# comando.net
KiCad netlist of a schematic drawn in EAGLE
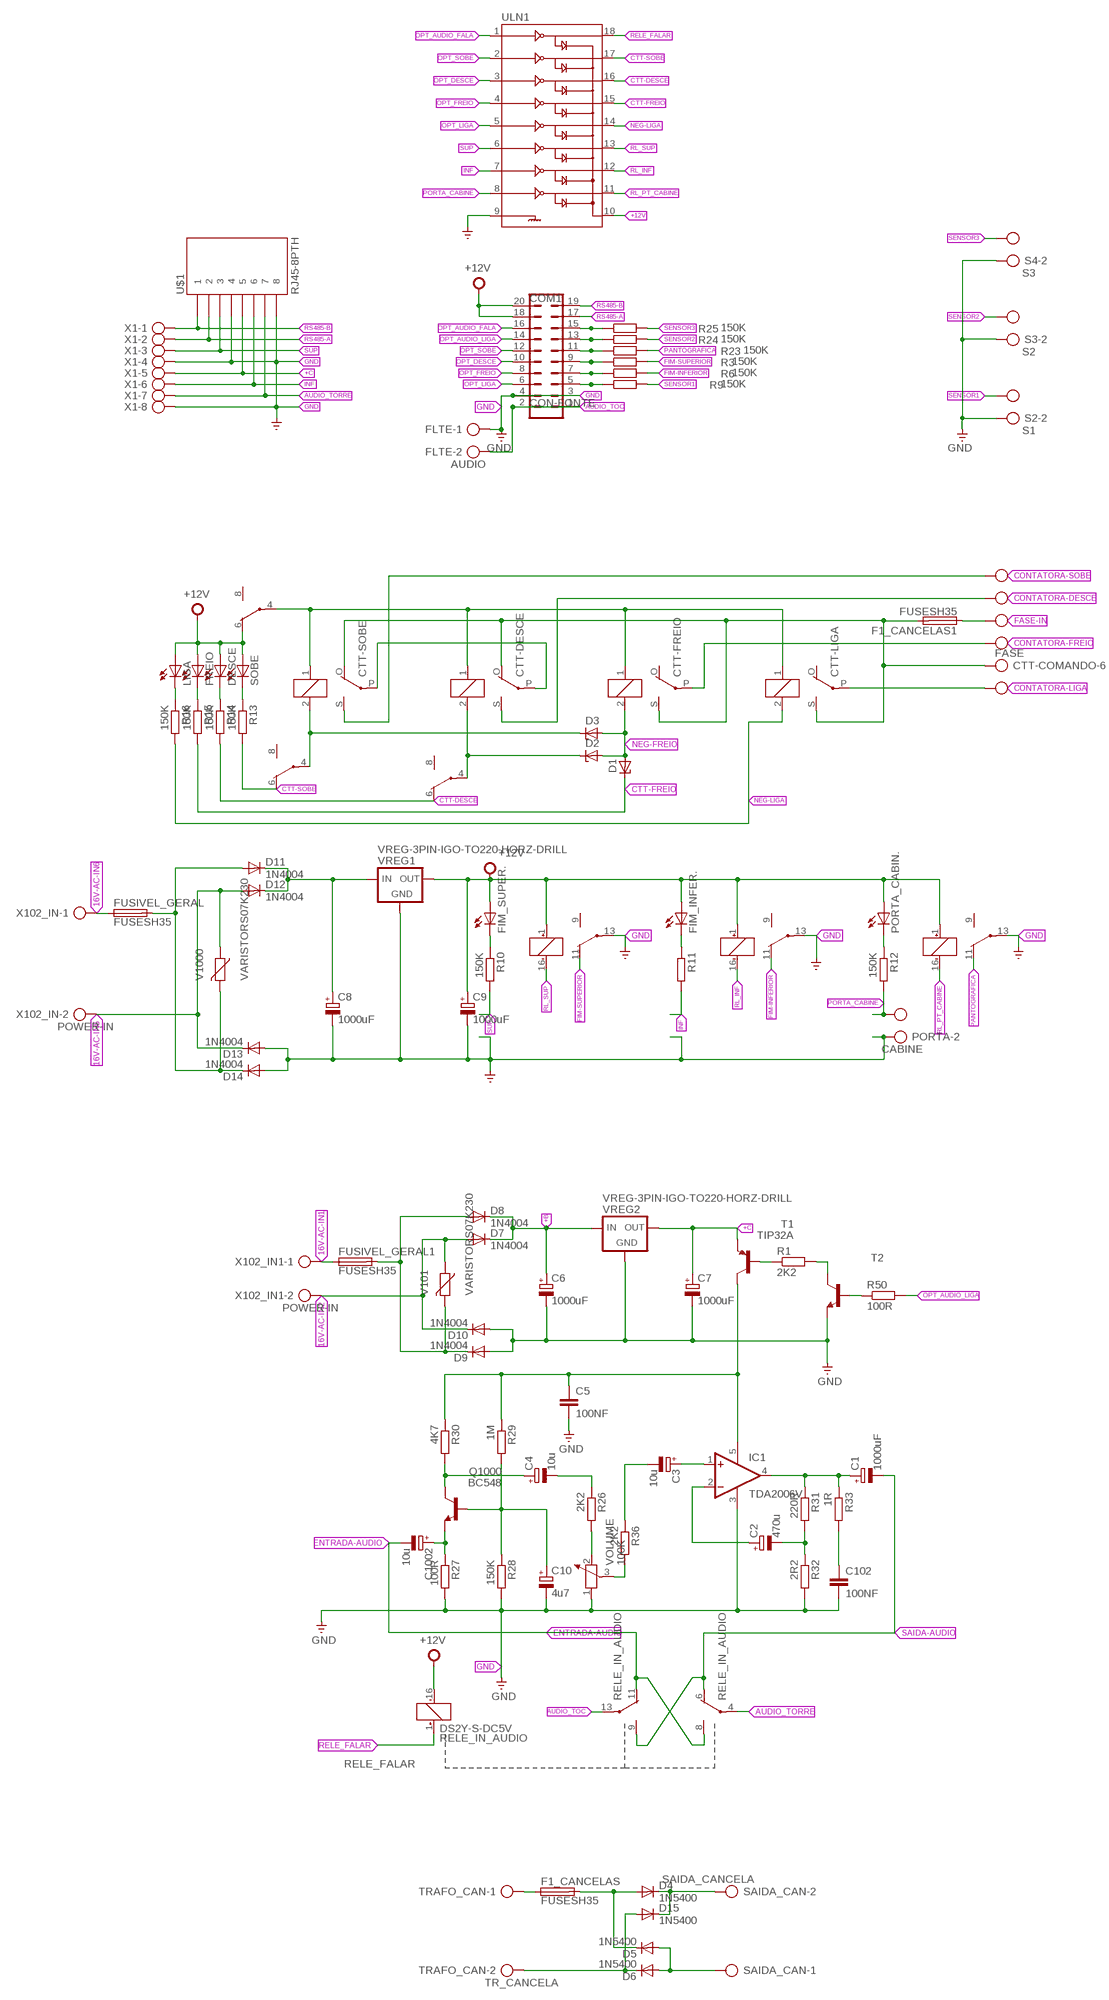
[diagram p0: schematic, sheet 1]

(export (version "E")
  (design (tool "Eeschema 10.0.6"))
  (components
    (comp (ref "C1")
      (value "1000uF")
      (footprint "eagle-import:TAP5-80")
      (libsource (lib "eagle-import") (part "CPOL-EUTAP5-80"))
    )
    (comp (ref "C2")
      (value "470u")
      (footprint "eagle-import:TAP5-80")
      (libsource (lib "eagle-import") (part "CPOL-EUTAP5-80"))
    )
    (comp (ref "C3")
      (value "10u")
      (footprint "eagle-import:TAP5-45")
      (libsource (lib "eagle-import") (part "CPOL-EUTAP5-45"))
    )
    (comp (ref "C4")
      (value "10u")
      (footprint "eagle-import:TAP5-45")
      (libsource (lib "eagle-import") (part "CPOL-EUTAP5-45"))
    )
    (comp (ref "C5")
      (value "100NF")
      (footprint "eagle-import:C050-030X075")
      (libsource (lib "eagle-import") (part "C-EU050-030X075"))
    )
    (comp (ref "C6")
      (value "1000uF")
      (footprint "eagle-import:TAP5-80")
      (libsource (lib "eagle-import") (part "CPOL-EUTAP5-80"))
    )
    (comp (ref "C7")
      (value "1000uF")
      (footprint "eagle-import:TAP5-80")
      (libsource (lib "eagle-import") (part "CPOL-EUTAP5-80"))
    )
    (comp (ref "C8")
      (value "1000uF")
      (footprint "eagle-import:TAP5-80")
      (libsource (lib "eagle-import") (part "CPOL-EUTAP5-80"))
    )
    (comp (ref "C9")
      (value "1000uF")
      (footprint "eagle-import:TAP5-80")
      (libsource (lib "eagle-import") (part "CPOL-EUTAP5-80"))
    )
    (comp (ref "C10")
      (value "4u7")
      (footprint "eagle-import:TAP5-45")
      (libsource (lib "eagle-import") (part "CPOL-EUTAP5-45"))
    )
    (comp (ref "C102")
      (value "100NF")
      (footprint "eagle-import:C050-030X075")
      (libsource (lib "eagle-import") (part "C-EU050-030X075"))
    )
    (comp (ref "C1002")
      (value "10u")
      (footprint "eagle-import:TAP5-45")
      (libsource (lib "eagle-import") (part "CPOL-EUTAP5-45"))
    )
    (comp (ref "COM1")
      (value "CON-FONTE")
      (footprint "eagle-import:ML20")
      (libsource (lib "eagle-import") (part "ML20"))
    )
    (comp (ref "CTT-COMANDO")
      (value "FASE")
      (footprint "eagle-import:AK500_6")
      (libsource (lib "eagle-import") (part "AK500/6"))
    )
    (comp (ref "CTT-DESCE")
      (value "G5L")
      (footprint "eagle-import:G5LE")
      (libsource (lib "eagle-import") (part "G5L"))
    )
    (comp (ref "CTT-FREIO")
      (value "G5L")
      (footprint "eagle-import:G5LE")
      (libsource (lib "eagle-import") (part "G5L"))
    )
    (comp (ref "CTT-LIGA")
      (value "G5L")
      (footprint "eagle-import:G5LE")
      (libsource (lib "eagle-import") (part "G5L"))
    )
    (comp (ref "CTT-SOBE")
      (value "G5L")
      (footprint "eagle-import:G5LE")
      (libsource (lib "eagle-import") (part "G5L"))
    )
    (comp (ref "D1")
      (value "ZENER-DIODEZD-7.5")
      (footprint "eagle-import:ZDIO-7.5")
      (libsource (lib "eagle-import") (part "ZENER-DIODEZD-7.5"))
    )
    (comp (ref "D2")
      (value "ZENER-DIODEZD-7.5")
      (footprint "eagle-import:ZDIO-7.5")
      (libsource (lib "eagle-import") (part "ZENER-DIODEZD-7.5"))
    )
    (comp (ref "D3")
      (value "ZENER-DIODEZD-7.5")
      (footprint "eagle-import:ZDIO-7.5")
      (libsource (lib "eagle-import") (part "ZENER-DIODEZD-7.5"))
    )
    (comp (ref "D4")
      (value "1N5400")
      (footprint "eagle-import:DO201-15")
      (libsource (lib "eagle-import") (part "1N5400"))
    )
    (comp (ref "D5")
      (value "1N5400")
      (footprint "eagle-import:DO201-15")
      (libsource (lib "eagle-import") (part "1N5400"))
    )
    (comp (ref "D6")
      (value "1N5400")
      (footprint "eagle-import:DO201-15")
      (libsource (lib "eagle-import") (part "1N5400"))
    )
    (comp (ref "D7")
      (value "1N4004")
      (footprint "eagle-import:DO41-10")
      (libsource (lib "eagle-import") (part "1N4004"))
    )
    (comp (ref "D8")
      (value "1N4004")
      (footprint "eagle-import:DO41-10")
      (libsource (lib "eagle-import") (part "1N4004"))
    )
    (comp (ref "D9")
      (value "1N4004")
      (footprint "eagle-import:DO41-10")
      (libsource (lib "eagle-import") (part "1N4004"))
    )
    (comp (ref "D10")
      (value "1N4004")
      (footprint "eagle-import:DO41-10")
      (libsource (lib "eagle-import") (part "1N4004"))
    )
    (comp (ref "D11")
      (value "1N4004")
      (footprint "eagle-import:DO41-10")
      (libsource (lib "eagle-import") (part "1N4004"))
    )
    (comp (ref "D12")
      (value "1N4004")
      (footprint "eagle-import:DO41-10")
      (libsource (lib "eagle-import") (part "1N4004"))
    )
    (comp (ref "D13")
      (value "1N4004")
      (footprint "eagle-import:DO41-10")
      (libsource (lib "eagle-import") (part "1N4004"))
    )
    (comp (ref "D14")
      (value "1N4004")
      (footprint "eagle-import:DO41-10")
      (libsource (lib "eagle-import") (part "1N4004"))
    )
    (comp (ref "D15")
      (value "1N5400")
      (footprint "eagle-import:DO201-15")
      (libsource (lib "eagle-import") (part "1N5400"))
    )
    (comp (ref "DESCE")
      (value "LED5MM")
      (footprint "eagle-import:LED5MM")
      (libsource (lib "eagle-import") (part "LED5MM"))
    )
    (comp (ref "F1_CANCELAS")
      (value "FUSESH35")
      (footprint "eagle-import:SH25")
      (libsource (lib "eagle-import") (part "FUSESH35"))
    )
    (comp (ref "F1_CANCELAS1")
      (value "FUSESH35")
      (footprint "eagle-import:SH25")
      (libsource (lib "eagle-import") (part "FUSESH35"))
    )
    (comp (ref "FIM_INFER.")
      (value "LED5MM")
      (footprint "eagle-import:LED5MM")
      (libsource (lib "eagle-import") (part "LED5MM"))
    )
    (comp (ref "FIM_SUPER.")
      (value "LED5MM")
      (footprint "eagle-import:LED5MM")
      (libsource (lib "eagle-import") (part "LED5MM"))
    )
    (comp (ref "FLTE")
      (value "AUDIO")
      (footprint "eagle-import:AK500_2")
      (libsource (lib "eagle-import") (part "AK500/2"))
    )
    (comp (ref "FREIO")
      (value "LED5MM")
      (footprint "eagle-import:LED5MM")
      (libsource (lib "eagle-import") (part "LED5MM"))
    )
    (comp (ref "FUSIVEL_GERAL")
      (value "FUSESH35")
      (footprint "eagle-import:SH25")
      (libsource (lib "eagle-import") (part "FUSESH35"))
    )
    (comp (ref "FUSIVEL_GERAL1")
      (value "FUSESH35")
      (footprint "eagle-import:SH25")
      (libsource (lib "eagle-import") (part "FUSESH35"))
    )
    (comp (ref "IC1")
      (value "TDA2006V")
      (footprint "eagle-import:CB360")
      (libsource (lib "eagle-import") (part "TDA2006V"))
    )
    (comp (ref "LIGA")
      (value "LED5MM")
      (footprint "eagle-import:LED5MM")
      (libsource (lib "eagle-import") (part "LED5MM"))
    )
    (comp (ref "PORTA")
      (value "CABINE")
      (footprint "eagle-import:AK500_2")
      (libsource (lib "eagle-import") (part "AK500/2"))
    )
    (comp (ref "PORTA_CABIN.")
      (value "LED5MM")
      (footprint "eagle-import:LED5MM")
      (libsource (lib "eagle-import") (part "LED5MM"))
    )
    (comp (ref "PORTA_CABINE")
      (value "DS2Y-S-DC5V")
      (footprint "eagle-import:DS2Y")
      (libsource (lib "eagle-import") (part "DS2Y-S-DC5V"))
    )
    (comp (ref "Q1000")
      (value "BC548")
      (footprint "eagle-import:TO92-EBC")
      (libsource (lib "eagle-import") (part "BC548"))
    )
    (comp (ref "R1")
      (value "2K2")
      (footprint "eagle-import:0207_10")
      (libsource (lib "eagle-import") (part "R-EU_0207/10"))
    )
    (comp (ref "R3")
      (value "150K")
      (footprint "eagle-import:0207_10")
      (libsource (lib "eagle-import") (part "R-EU_0207/10"))
    )
    (comp (ref "R6")
      (value "150K")
      (footprint "eagle-import:0207_10")
      (libsource (lib "eagle-import") (part "R-EU_0207/10"))
    )
    (comp (ref "R9")
      (value "150K")
      (footprint "eagle-import:0207_10")
      (libsource (lib "eagle-import") (part "R-EU_0207/10"))
    )
    (comp (ref "R10")
      (value "150K")
      (footprint "eagle-import:0207_10")
      (libsource (lib "eagle-import") (part "R-EU_0207/10"))
    )
    (comp (ref "R11")
      (value "150K")
      (footprint "eagle-import:0207_10")
      (libsource (lib "eagle-import") (part "R-EU_0207/10"))
    )
    (comp (ref "R12")
      (value "150K")
      (footprint "eagle-import:0207_10")
      (libsource (lib "eagle-import") (part "R-EU_0207/10"))
    )
    (comp (ref "R13")
      (value "150K")
      (footprint "eagle-import:0207_10")
      (libsource (lib "eagle-import") (part "R-EU_0207/10"))
    )
    (comp (ref "R14")
      (value "150K")
      (footprint "eagle-import:0207_10")
      (libsource (lib "eagle-import") (part "R-EU_0207/10"))
    )
    (comp (ref "R15")
      (value "150K")
      (footprint "eagle-import:0207_10")
      (libsource (lib "eagle-import") (part "R-EU_0207/10"))
    )
    (comp (ref "R16")
      (value "150K")
      (footprint "eagle-import:0207_10")
      (libsource (lib "eagle-import") (part "R-EU_0207/10"))
    )
    (comp (ref "R23")
      (value "150K")
      (footprint "eagle-import:0207_10")
      (libsource (lib "eagle-import") (part "R-EU_0207/10"))
    )
    (comp (ref "R24")
      (value "150K")
      (footprint "eagle-import:0207_10")
      (libsource (lib "eagle-import") (part "R-EU_0207/10"))
    )
    (comp (ref "R25")
      (value "150K")
      (footprint "eagle-import:0207_10")
      (libsource (lib "eagle-import") (part "R-EU_0207/10"))
    )
    (comp (ref "R26")
      (value "2K2")
      (footprint "eagle-import:0207_10")
      (libsource (lib "eagle-import") (part "R-EU_0207/10"))
    )
    (comp (ref "R27")
      (value "100R")
      (footprint "eagle-import:0207_10")
      (libsource (lib "eagle-import") (part "R-EU_0207/10"))
    )
    (comp (ref "R28")
      (value "150K")
      (footprint "eagle-import:0207_10")
      (libsource (lib "eagle-import") (part "R-EU_0207/10"))
    )
    (comp (ref "R29")
      (value "1M")
      (footprint "eagle-import:0207_10")
      (libsource (lib "eagle-import") (part "R-EU_0207/10"))
    )
    (comp (ref "R30")
      (value "4K7")
      (footprint "eagle-import:0207_10")
      (libsource (lib "eagle-import") (part "R-EU_0207/10"))
    )
    (comp (ref "R31")
      (value "220R")
      (footprint "eagle-import:0207_10")
      (libsource (lib "eagle-import") (part "R-EU_0207/10"))
    )
    (comp (ref "R32")
      (value "2R2")
      (footprint "eagle-import:0207_10")
      (libsource (lib "eagle-import") (part "R-EU_0207/10"))
    )
    (comp (ref "R33")
      (value "1R")
      (footprint "eagle-import:0207_10")
      (libsource (lib "eagle-import") (part "R-EU_0207/10"))
    )
    (comp (ref "R36")
      (value "2K2")
      (footprint "eagle-import:0207_10")
      (libsource (lib "eagle-import") (part "R-EU_0207/10"))
    )
    (comp (ref "R50")
      (value "100R")
      (footprint "eagle-import:0207_10")
      (libsource (lib "eagle-import") (part "R-EU_0207/10"))
    )
    (comp (ref "RELE_IN_AUDIO")
      (value "DS2Y-S-DC5V")
      (footprint "eagle-import:DS2Y")
      (libsource (lib "eagle-import") (part "DS2Y-S-DC5V"))
    )
    (comp (ref "RL_FIM_INFERIOR")
      (value "DS2Y-S-DC5V")
      (footprint "eagle-import:DS2Y")
      (libsource (lib "eagle-import") (part "DS2Y-S-DC5V"))
    )
    (comp (ref "RL_FIM_SUPERIOR")
      (value "DS2Y-S-DC5V")
      (footprint "eagle-import:DS2Y")
      (libsource (lib "eagle-import") (part "DS2Y-S-DC5V"))
    )
    (comp (ref "S2")
      (value "S1")
      (footprint "eagle-import:AK500_2")
      (libsource (lib "eagle-import") (part "AK500/2"))
    )
    (comp (ref "S3")
      (value "S2")
      (footprint "eagle-import:AK500_2")
      (libsource (lib "eagle-import") (part "AK500/2"))
    )
    (comp (ref "S4")
      (value "S3")
      (footprint "eagle-import:AK500_2")
      (libsource (lib "eagle-import") (part "AK500/2"))
    )
    (comp (ref "SAIDA_CAN")
      (value "SAIDA_CANCELA")
      (footprint "eagle-import:AK500_2")
      (libsource (lib "eagle-import") (part "AK500/2"))
    )
    (comp (ref "SOBE")
      (value "LED5MM")
      (footprint "eagle-import:LED5MM")
      (libsource (lib "eagle-import") (part "LED5MM"))
    )
    (comp (ref "T1")
      (value "TIP32A")
      (footprint "eagle-import:TO220")
      (libsource (lib "eagle-import") (part "TIP32A"))
    )
    (comp (ref "T2")
      (value "BC548-NPN-TO92-CBE")
      (footprint "eagle-import:TO92-CBE")
      (libsource (lib "eagle-import") (part "-NPN-TO92-CBEBC548"))
    )
    (comp (ref "TRAFO_CAN")
      (value "TR_CANCELA")
      (footprint "eagle-import:AK500_2")
      (libsource (lib "eagle-import") (part "AK500/2"))
    )
    (comp (ref "U$1")
      (value "RJ45-8PTH")
      (footprint "eagle-import:RJ45-8")
      (libsource (lib "eagle-import") (part "RJ45-8PTH"))
    )
    (comp (ref "ULN1")
      (value "ULN2803DIP")
      (footprint "eagle-import:DIL18")
      (libsource (lib "eagle-import") (part "ULN2803DIP"))
    )
    (comp (ref "V101")
      (value "VARISTORS07K230")
      (footprint "eagle-import:S07K230")
      (libsource (lib "eagle-import") (part "VARISTORS07K230"))
    )
    (comp (ref "V1000")
      (value "VARISTORS07K230")
      (footprint "eagle-import:S07K230")
      (libsource (lib "eagle-import") (part "VARISTORS07K230"))
    )
    (comp (ref "VOLUME")
      (value "100K")
      (footprint "eagle-import:PT-10")
      (libsource (lib "eagle-import") (part "POTENTIOMETER_PT-10"))
    )
    (comp (ref "VREG1")
      (value "VREG-3PIN-IGO-TO220-HORZ-DRILL")
      (footprint "eagle-import:TO220-HORZ-DRILL")
      (libsource (lib "eagle-import") (part "VREG-3PIN-IGO-TO220-HORZ-DRILL"))
    )
    (comp (ref "VREG2")
      (value "VREG-3PIN-IGO-TO220-HORZ-DRILL")
      (footprint "eagle-import:TO220-HORZ-DRILL")
      (libsource (lib "eagle-import") (part "VREG-3PIN-IGO-TO220-HORZ-DRILL"))
    )
    (comp (ref "X1")
      (value "RS485_CNT")
      (footprint "eagle-import:AK500_8")
      (libsource (lib "eagle-import") (part "AK500/8"))
    )
    (comp (ref "X102_IN")
      (value "POWER-IN")
      (footprint "eagle-import:AK500_2")
      (libsource (lib "eagle-import") (part "AK500/2"))
    )
    (comp (ref "X102_IN1")
      (value "POWER-IN")
      (footprint "eagle-import:AK500_2")
      (libsource (lib "eagle-import") (part "AK500/2"))
    )
  )
  (nets
    (net (code "1") (name "+12V") (class "Default")
      (node (ref "C9") (pin "+") (pinfunction "+_+") (pintype "passive"))
      (node (ref "COM1") (pin "18") (pinfunction "18_18") (pintype "passive"))
      (node (ref "COM1") (pin "20") (pinfunction "20_20") (pintype "passive"))
      (node (ref "DESCE") (pin "A") (pinfunction "A_A") (pintype "passive"))
      (node (ref "FIM_INFER.") (pin "A") (pinfunction "A_A") (pintype "passive"))
      (node (ref "FIM_SUPER.") (pin "A") (pinfunction "A_A") (pintype "passive"))
      (node (ref "FREIO") (pin "A") (pinfunction "A_A") (pintype "passive"))
      (node (ref "LIGA") (pin "A") (pinfunction "A_A") (pintype "passive"))
      (node (ref "PORTA_CABIN.") (pin "A") (pinfunction "A_A") (pintype "passive"))
      (node (ref "PORTA_CABINE") (pin "1") (pinfunction "+_1") (pintype "passive"))
      (node (ref "PORTA_CABINE") (pin "6") (pinfunction "O_6") (pintype "passive"))
      (node (ref "RELE_IN_AUDIO") (pin "16") (pinfunction "-_16") (pintype "passive"))
      (node (ref "RL_FIM_INFERIOR") (pin "1") (pinfunction "+_1") (pintype "passive"))
      (node (ref "RL_FIM_SUPERIOR") (pin "1") (pinfunction "+_1") (pintype "passive"))
      (node (ref "SOBE") (pin "A") (pinfunction "A_A") (pintype "passive"))
      (node (ref "ULN1") (pin "10") (pinfunction "10_10") (pintype "bidirectional"))
      (node (ref "VREG1") (pin "3") (pinfunction "OUT_3") (pintype "power_in"))
    )
    (net (code "2") (name "+B") (class "Default")
      (node (ref "C6") (pin "+") (pinfunction "+_+") (pintype "passive"))
      (node (ref "D7") (pin "C") (pinfunction "C_C") (pintype "passive"))
      (node (ref "D8") (pin "C") (pinfunction "C_C") (pintype "passive"))
      (node (ref "VREG2") (pin "1") (pinfunction "IN_1") (pintype "power_in"))
    )
    (net (code "3") (name "+C") (class "Default")
      (node (ref "C7") (pin "+") (pinfunction "+_+") (pintype "passive"))
      (node (ref "T1") (pin "3") (pinfunction "E_3") (pintype "passive"))
      (node (ref "U$1") (pin "5") (pinfunction "5_5") (pintype "bidirectional"))
      (node (ref "VREG2") (pin "3") (pinfunction "OUT_3") (pintype "power_in"))
      (node (ref "X1") (pin "5") (pinfunction "KL_5") (pintype "passive"))
    )
    (net (code "4") (name "16V-AC-IN1") (class "Default")
      (node (ref "FUSIVEL_GERAL1") (pin "1") (pinfunction "1_1") (pintype "passive"))
      (node (ref "X102_IN1") (pin "1") (pinfunction "KL_1") (pintype "passive"))
    )
    (net (code "5") (name "16V-AC-IN2") (class "Default")
      (node (ref "D10") (pin "C") (pinfunction "C_C") (pintype "passive"))
      (node (ref "D7") (pin "A") (pinfunction "A_A") (pintype "passive"))
      (node (ref "V101") (pin "1") (pinfunction "1_1") (pintype "passive"))
      (node (ref "X102_IN1") (pin "2") (pinfunction "KL_2") (pintype "passive"))
    )
    (net (code "6") (name "16V-AC-IN5") (class "Default")
      (node (ref "D12") (pin "A") (pinfunction "A_A") (pintype "passive"))
      (node (ref "D13") (pin "C") (pinfunction "C_C") (pintype "passive"))
      (node (ref "V1000") (pin "1") (pinfunction "1_1") (pintype "passive"))
      (node (ref "X102_IN") (pin "2") (pinfunction "KL_2") (pintype "passive"))
    )
    (net (code "7") (name "16V-AC-IN6") (class "Default")
      (node (ref "FUSIVEL_GERAL") (pin "1") (pinfunction "1_1") (pintype "passive"))
      (node (ref "X102_IN") (pin "1") (pinfunction "KL_1") (pintype "passive"))
    )
    (net (code "8") (name "AUDIO_TOC") (class "Default")
      (node (ref "COM1") (pin "1") (pinfunction "1_1") (pintype "passive"))
      (node (ref "COM1") (pin "2") (pinfunction "2_2") (pintype "passive"))
      (node (ref "FLTE") (pin "2") (pinfunction "KL_2") (pintype "passive"))
      (node (ref "RELE_IN_AUDIO") (pin "13") (pinfunction "P_13") (pintype "passive"))
    )
    (net (code "9") (name "AUDIO_TORRE") (class "Default")
      (node (ref "RELE_IN_AUDIO") (pin "4") (pinfunction "P_4") (pintype "passive"))
      (node (ref "U$1") (pin "7") (pinfunction "7_7") (pintype "bidirectional"))
      (node (ref "X1") (pin "7") (pinfunction "KL_7") (pintype "passive"))
    )
    (net (code "10") (name "CONTATORA-DESCE") (class "Default")
      (node (ref "CTT-COMANDO") (pin "4") (pinfunction "KL_4") (pintype "passive"))
      (node (ref "CTT-DESCE") (pin "S") (pinfunction "S_S") (pintype "passive"))
    )
    (net (code "11") (name "CONTATORA-FREIO") (class "Default")
      (node (ref "CTT-COMANDO") (pin "3") (pinfunction "KL_3") (pintype "passive"))
      (node (ref "CTT-FREIO") (pin "P") (pinfunction "P_P") (pintype "passive"))
    )
    (net (code "12") (name "CONTATORA-LIGA") (class "Default")
      (node (ref "CTT-COMANDO") (pin "2") (pinfunction "KL_2") (pintype "passive"))
      (node (ref "CTT-LIGA") (pin "P") (pinfunction "P_P") (pintype "passive"))
    )
    (net (code "13") (name "CONTATORA-SOBE") (class "Default")
      (node (ref "CTT-COMANDO") (pin "5") (pinfunction "KL_5") (pintype "passive"))
      (node (ref "CTT-SOBE") (pin "S") (pinfunction "S_S") (pintype "passive"))
    )
    (net (code "14") (name "CTT-DESCE") (class "Default")
      (node (ref "R14") (pin "2") (pinfunction "2_2") (pintype "passive"))
      (node (ref "RL_FIM_INFERIOR") (pin "6") (pinfunction "O_6") (pintype "passive"))
      (node (ref "ULN1") (pin "16") (pinfunction "16_16") (pintype "bidirectional"))
    )
    (net (code "15") (name "CTT-FREIO") (class "Default")
      (node (ref "D1") (pin "C") (pinfunction "C_C") (pintype "passive"))
      (node (ref "R15") (pin "2") (pinfunction "2_2") (pintype "passive"))
      (node (ref "ULN1") (pin "15") (pinfunction "15_15") (pintype "bidirectional"))
    )
    (net (code "16") (name "CTT-SOBE") (class "Default")
      (node (ref "R13") (pin "2") (pinfunction "2_2") (pintype "passive"))
      (node (ref "RL_FIM_SUPERIOR") (pin "6") (pinfunction "O_6") (pintype "passive"))
      (node (ref "ULN1") (pin "17") (pinfunction "17_17") (pintype "bidirectional"))
    )
    (net (code "17") (name "ENTRADA-AUDIO") (class "Default")
      (node (ref "C1002") (pin "-") (pinfunction "-_-") (pintype "passive"))
      (node (ref "RELE_IN_AUDIO") (pin "11") (pinfunction "O_11") (pintype "passive"))
      (node (ref "RELE_IN_AUDIO") (pin "8") (pinfunction "S_8") (pintype "passive"))
    )
    (net (code "18") (name "FASE-IN") (class "Default")
      (node (ref "CTT-COMANDO") (pin "1") (pinfunction "KL_1") (pintype "passive"))
      (node (ref "F1_CANCELAS1") (pin "1") (pinfunction "1_1") (pintype "passive"))
    )
    (net (code "19") (name "FIM-INFERIOR") (class "Default")
      (node (ref "R6") (pin "2") (pinfunction "2_2") (pintype "passive"))
      (node (ref "RL_FIM_INFERIOR") (pin "11") (pinfunction "O_11") (pintype "passive"))
    )
    (net (code "20") (name "FIM-SUPERIOR") (class "Default")
      (node (ref "R3") (pin "2") (pinfunction "2_2") (pintype "passive"))
      (node (ref "RL_FIM_SUPERIOR") (pin "11") (pinfunction "O_11") (pintype "passive"))
    )
    (net (code "21") (name "GND") (class "Default")
      (node (ref "C10") (pin "-") (pinfunction "-_-") (pintype "passive"))
      (node (ref "C102") (pin "2") (pinfunction "2_2") (pintype "passive"))
      (node (ref "C5") (pin "2") (pinfunction "2_2") (pintype "passive"))
      (node (ref "C6") (pin "-") (pinfunction "-_-") (pintype "passive"))
      (node (ref "C7") (pin "-") (pinfunction "-_-") (pintype "passive"))
      (node (ref "C8") (pin "-") (pinfunction "-_-") (pintype "passive"))
      (node (ref "C9") (pin "-") (pinfunction "-_-") (pintype "passive"))
      (node (ref "COM1") (pin "3") (pinfunction "3_3") (pintype "passive"))
      (node (ref "COM1") (pin "4") (pinfunction "4_4") (pintype "passive"))
      (node (ref "D10") (pin "A") (pinfunction "A_A") (pintype "passive"))
      (node (ref "D13") (pin "A") (pinfunction "A_A") (pintype "passive"))
      (node (ref "D14") (pin "A") (pinfunction "A_A") (pintype "passive"))
      (node (ref "D9") (pin "A") (pinfunction "A_A") (pintype "passive"))
      (node (ref "FLTE") (pin "1") (pinfunction "KL_1") (pintype "passive"))
      (node (ref "IC1") (pin "3") (pinfunction "V-_3") (pintype "power_in"))
      (node (ref "PORTA") (pin "2") (pinfunction "KL_2") (pintype "passive"))
      (node (ref "PORTA_CABINE") (pin "13") (pinfunction "P_13") (pintype "passive"))
      (node (ref "R27") (pin "2") (pinfunction "2_2") (pintype "passive"))
      (node (ref "R28") (pin "2") (pinfunction "2_2") (pintype "passive"))
      (node (ref "R32") (pin "2") (pinfunction "2_2") (pintype "passive"))
      (node (ref "RL_FIM_INFERIOR") (pin "13") (pinfunction "P_13") (pintype "passive"))
      (node (ref "RL_FIM_SUPERIOR") (pin "13") (pinfunction "P_13") (pintype "passive"))
      (node (ref "S2") (pin "2") (pinfunction "KL_2") (pintype "passive"))
      (node (ref "S3") (pin "2") (pinfunction "KL_2") (pintype "passive"))
      (node (ref "S4") (pin "2") (pinfunction "KL_2") (pintype "passive"))
      (node (ref "T2") (pin "E") (pinfunction "E_E") (pintype "passive"))
      (node (ref "U$1") (pin "4") (pinfunction "4_4") (pintype "bidirectional"))
      (node (ref "U$1") (pin "8") (pinfunction "8_8") (pintype "bidirectional"))
      (node (ref "ULN1") (pin "9") (pinfunction "9_9") (pintype "bidirectional"))
      (node (ref "VOLUME") (pin "1") (pinfunction "1_1") (pintype "passive"))
      (node (ref "VREG1") (pin "2") (pinfunction "GND_2") (pintype "power_in"))
      (node (ref "VREG2") (pin "2") (pinfunction "GND_2") (pintype "power_in"))
      (node (ref "X1") (pin "4") (pinfunction "KL_4") (pintype "passive"))
      (node (ref "X1") (pin "8") (pinfunction "KL_8") (pintype "passive"))
    )
    (net (code "22") (name "INF") (class "Default")
      (node (ref "R11") (pin "2") (pinfunction "2_2") (pintype "passive"))
      (node (ref "U$1") (pin "6") (pinfunction "6_6") (pintype "bidirectional"))
      (node (ref "ULN1") (pin "7") (pinfunction "7_7") (pintype "bidirectional"))
      (node (ref "X1") (pin "6") (pinfunction "KL_6") (pintype "passive"))
    )
    (net (code "23") (name "NEG-FREIO") (class "Default")
      (node (ref "CTT-FREIO") (pin "2") (pinfunction "2_2") (pintype "passive"))
      (node (ref "D1") (pin "A") (pinfunction "A_A") (pintype "passive"))
      (node (ref "D2") (pin "A") (pinfunction "A_A") (pintype "passive"))
      (node (ref "D3") (pin "A") (pinfunction "A_A") (pintype "passive"))
    )
    (net (code "24") (name "NEG-LIGA") (class "Default")
      (node (ref "CTT-LIGA") (pin "2") (pinfunction "2_2") (pintype "passive"))
      (node (ref "R16") (pin "2") (pinfunction "2_2") (pintype "passive"))
      (node (ref "ULN1") (pin "14") (pinfunction "14_14") (pintype "bidirectional"))
    )
    (net (code "25") (name "Net-(C2-Pad-)") (class "Default")
      (node (ref "C2") (pin "-") (pinfunction "-_-") (pintype "passive"))
      (node (ref "R31") (pin "2") (pinfunction "2_2") (pintype "passive"))
      (node (ref "R32") (pin "1") (pinfunction "1_1") (pintype "passive"))
    )
    (net (code "26") (name "Net-(C3-Pad-)") (class "Default")
      (node (ref "C3") (pin "-") (pinfunction "-_-") (pintype "passive"))
      (node (ref "R36") (pin "1") (pinfunction "1_1") (pintype "passive"))
    )
    (net (code "27") (name "Net-(C4-Pad+)") (class "Default")
      (node (ref "C4") (pin "+") (pinfunction "+_+") (pintype "passive"))
      (node (ref "Q1000") (pin "C") (pinfunction "C_C") (pintype "passive"))
      (node (ref "R30") (pin "2") (pinfunction "2_2") (pintype "passive"))
    )
    (net (code "28") (name "Net-(C4-Pad-)") (class "Default")
      (node (ref "C4") (pin "-") (pinfunction "-_-") (pintype "passive"))
      (node (ref "R26") (pin "1") (pinfunction "1_1") (pintype "passive"))
    )
    (net (code "29") (name "Net-(C10-Pad+)") (class "Default")
      (node (ref "C10") (pin "+") (pinfunction "+_+") (pintype "passive"))
      (node (ref "Q1000") (pin "B") (pinfunction "B_B") (pintype "passive"))
      (node (ref "R28") (pin "1") (pinfunction "1_1") (pintype "passive"))
      (node (ref "R29") (pin "2") (pinfunction "2_2") (pintype "passive"))
    )
    (net (code "30") (name "Net-(C102-Pad1)") (class "Default")
      (node (ref "C102") (pin "1") (pinfunction "1_1") (pintype "passive"))
      (node (ref "R33") (pin "2") (pinfunction "2_2") (pintype "passive"))
    )
    (net (code "31") (name "Net-(C1002-Pad+)") (class "Default")
      (node (ref "C1002") (pin "+") (pinfunction "+_+") (pintype "passive"))
      (node (ref "Q1000") (pin "E") (pinfunction "E_E") (pintype "passive"))
      (node (ref "R27") (pin "1") (pinfunction "1_1") (pintype "passive"))
    )
    (net (code "32") (name "Net-(COM1-Pad5)") (class "Default")
      (node (ref "COM1") (pin "5") (pinfunction "5_5") (pintype "passive"))
      (node (ref "R9") (pin "1") (pinfunction "1_1") (pintype "passive"))
    )
    (net (code "33") (name "Net-(COM1-Pad7)") (class "Default")
      (node (ref "COM1") (pin "7") (pinfunction "7_7") (pintype "passive"))
      (node (ref "R6") (pin "1") (pinfunction "1_1") (pintype "passive"))
    )
    (net (code "34") (name "Net-(COM1-Pad9)") (class "Default")
      (node (ref "COM1") (pin "9") (pinfunction "9_9") (pintype "passive"))
      (node (ref "R3") (pin "1") (pinfunction "1_1") (pintype "passive"))
    )
    (net (code "35") (name "Net-(COM1-Pad11)") (class "Default")
      (node (ref "COM1") (pin "11") (pinfunction "11_11") (pintype "passive"))
      (node (ref "R23") (pin "1") (pinfunction "1_1") (pintype "passive"))
    )
    (net (code "36") (name "Net-(COM1-Pad13)") (class "Default")
      (node (ref "COM1") (pin "13") (pinfunction "13_13") (pintype "passive"))
      (node (ref "R24") (pin "1") (pinfunction "1_1") (pintype "passive"))
    )
    (net (code "37") (name "Net-(COM1-Pad15)") (class "Default")
      (node (ref "COM1") (pin "15") (pinfunction "15_15") (pintype "passive"))
      (node (ref "R25") (pin "1") (pinfunction "1_1") (pintype "passive"))
    )
    (net (code "38") (name "Net-(CTT-COMANDOF-KL)") (class "Default")
      (node (ref "CTT-COMANDO") (pin "6") (pinfunction "KL_6") (pintype "passive"))
      (node (ref "CTT-DESCE") (pin "O") (pinfunction "O_O") (pintype "passive"))
      (node (ref "CTT-FREIO") (pin "S") (pinfunction "S_S") (pintype "passive"))
      (node (ref "CTT-LIGA") (pin "S") (pinfunction "S_S") (pintype "passive"))
      (node (ref "CTT-SOBE") (pin "O") (pinfunction "O_O") (pintype "passive"))
      (node (ref "F1_CANCELAS1") (pin "2") (pinfunction "2_2") (pintype "passive"))
    )
    (net (code "39") (name "Net-(CTT-DESCE-PadP)") (class "Default")
      (node (ref "CTT-DESCE") (pin "P") (pinfunction "P_P") (pintype "passive"))
      (node (ref "CTT-SOBE") (pin "P") (pinfunction "P_P") (pintype "passive"))
    )
    (net (code "40") (name "Net-(D4-PadA)") (class "Default")
      (node (ref "D4") (pin "A") (pinfunction "A_A") (pintype "passive"))
      (node (ref "D5") (pin "C") (pinfunction "C_C") (pintype "passive"))
      (node (ref "F1_CANCELAS") (pin "2") (pinfunction "2_2") (pintype "passive"))
    )
    (net (code "41") (name "Net-(D8-PadA)") (class "Default")
      (node (ref "D8") (pin "A") (pinfunction "A_A") (pintype "passive"))
      (node (ref "D9") (pin "C") (pinfunction "C_C") (pintype "passive"))
      (node (ref "FUSIVEL_GERAL1") (pin "2") (pinfunction "2_2") (pintype "passive"))
      (node (ref "V101") (pin "2") (pinfunction "2_2") (pintype "passive"))
    )
    (net (code "42") (name "Net-(D11-PadA)") (class "Default")
      (node (ref "D11") (pin "A") (pinfunction "A_A") (pintype "passive"))
      (node (ref "D14") (pin "C") (pinfunction "C_C") (pintype "passive"))
      (node (ref "FUSIVEL_GERAL") (pin "2") (pinfunction "2_2") (pintype "passive"))
      (node (ref "V1000") (pin "2") (pinfunction "2_2") (pintype "passive"))
    )
    (net (code "43") (name "Net-(DESCE-C)") (class "Default")
      (node (ref "DESCE") (pin "K") (pinfunction "C_K") (pintype "passive"))
      (node (ref "R14") (pin "1") (pinfunction "1_1") (pintype "passive"))
    )
    (net (code "44") (name "Net-(FIM_INFER.-C)") (class "Default")
      (node (ref "FIM_INFER.") (pin "K") (pinfunction "C_K") (pintype "passive"))
      (node (ref "R11") (pin "1") (pinfunction "1_1") (pintype "passive"))
    )
    (net (code "45") (name "Net-(FIM_SUPER.-C)") (class "Default")
      (node (ref "FIM_SUPER.") (pin "K") (pinfunction "C_K") (pintype "passive"))
      (node (ref "R10") (pin "1") (pinfunction "1_1") (pintype "passive"))
    )
    (net (code "46") (name "Net-(FREIO-C)") (class "Default")
      (node (ref "FREIO") (pin "K") (pinfunction "C_K") (pintype "passive"))
      (node (ref "R15") (pin "1") (pinfunction "1_1") (pintype "passive"))
    )
    (net (code "47") (name "Net-(IC1-+IN)") (class "Default")
      (node (ref "C3") (pin "+") (pinfunction "+_+") (pintype "passive"))
      (node (ref "IC1") (pin "1") (pinfunction "+IN_1") (pintype "input"))
    )
    (net (code "48") (name "Net-(IC1--IN)") (class "Default")
      (node (ref "C2") (pin "+") (pinfunction "+_+") (pintype "passive"))
      (node (ref "IC1") (pin "2") (pinfunction "-IN_2") (pintype "input"))
    )
    (net (code "49") (name "Net-(IC1-OUT)") (class "Default")
      (node (ref "C1") (pin "+") (pinfunction "+_+") (pintype "passive"))
      (node (ref "IC1") (pin "4") (pinfunction "OUT_4") (pintype "output"))
      (node (ref "R31") (pin "1") (pinfunction "1_1") (pintype "passive"))
      (node (ref "R33") (pin "1") (pinfunction "1_1") (pintype "passive"))
    )
    (net (code "50") (name "Net-(IC1-V+)") (class "Default")
      (node (ref "C5") (pin "1") (pinfunction "1_1") (pintype "passive"))
      (node (ref "IC1") (pin "5") (pinfunction "V+_5") (pintype "power_in"))
      (node (ref "R29") (pin "1") (pinfunction "1_1") (pintype "passive"))
      (node (ref "R30") (pin "1") (pinfunction "1_1") (pintype "passive"))
      (node (ref "T1") (pin "2") (pinfunction "C_2") (pintype "passive"))
    )
    (net (code "51") (name "Net-(LIGA-C)") (class "Default")
      (node (ref "LIGA") (pin "K") (pinfunction "C_K") (pintype "passive"))
      (node (ref "R16") (pin "1") (pinfunction "1_1") (pintype "passive"))
    )
    (net (code "52") (name "Net-(PORTA_CABIN.-C)") (class "Default")
      (node (ref "PORTA_CABIN.") (pin "K") (pinfunction "C_K") (pintype "passive"))
      (node (ref "R12") (pin "1") (pinfunction "1_1") (pintype "passive"))
    )
    (net (code "53") (name "Net-(PORTA_CABINEB-P)") (class "Default")
      (node (ref "CTT-DESCE") (pin "1") (pinfunction "1_1") (pintype "passive"))
      (node (ref "CTT-FREIO") (pin "1") (pinfunction "1_1") (pintype "passive"))
      (node (ref "CTT-LIGA") (pin "1") (pinfunction "1_1") (pintype "passive"))
      (node (ref "CTT-SOBE") (pin "1") (pinfunction "1_1") (pintype "passive"))
      (node (ref "PORTA_CABINE") (pin "4") (pinfunction "P_4") (pintype "passive"))
    )
    (net (code "54") (name "Net-(R1-Pad2)") (class "Default")
      (node (ref "R1") (pin "2") (pinfunction "2_2") (pintype "passive"))
      (node (ref "T2") (pin "C") (pinfunction "C_C") (pintype "passive"))
    )
    (net (code "55") (name "Net-(R26-Pad2)") (class "Default")
      (node (ref "R26") (pin "2") (pinfunction "2_2") (pintype "passive"))
      (node (ref "VOLUME") (pin "2") (pinfunction "2_2") (pintype "passive"))
    )
    (net (code "56") (name "Net-(R36-Pad2)") (class "Default")
      (node (ref "R36") (pin "2") (pinfunction "2_2") (pintype "passive"))
      (node (ref "VOLUME") (pin "3") (pinfunction "3_3") (pintype "passive"))
    )
    (net (code "57") (name "Net-(R50-Pad1)") (class "Default")
      (node (ref "R50") (pin "1") (pinfunction "1_1") (pintype "passive"))
      (node (ref "T2") (pin "B") (pinfunction "B_B") (pintype "passive"))
    )
    (net (code "58") (name "Net-(RL_FIM_INFERIORB-P)") (class "Default")
      (node (ref "CTT-DESCE") (pin "2") (pinfunction "2_2") (pintype "passive"))
      (node (ref "D2") (pin "C") (pinfunction "C_C") (pintype "passive"))
      (node (ref "RL_FIM_INFERIOR") (pin "4") (pinfunction "P_4") (pintype "passive"))
    )
    (net (code "59") (name "Net-(RL_FIM_SUPERIORB-P)") (class "Default")
      (node (ref "CTT-SOBE") (pin "2") (pinfunction "2_2") (pintype "passive"))
      (node (ref "D3") (pin "C") (pinfunction "C_C") (pintype "passive"))
      (node (ref "RL_FIM_SUPERIOR") (pin "4") (pinfunction "P_4") (pintype "passive"))
    )
    (net (code "60") (name "Net-(SAIDA_CANA-KL)") (class "Default")
      (node (ref "D5") (pin "A") (pinfunction "A_A") (pintype "passive"))
      (node (ref "D6") (pin "A") (pinfunction "A_A") (pintype "passive"))
      (node (ref "SAIDA_CAN") (pin "1") (pinfunction "KL_1") (pintype "passive"))
    )
    (net (code "61") (name "Net-(SAIDA_CANB-KL)") (class "Default")
      (node (ref "D15") (pin "C") (pinfunction "C_C") (pintype "passive"))
      (node (ref "D4") (pin "C") (pinfunction "C_C") (pintype "passive"))
      (node (ref "SAIDA_CAN") (pin "2") (pinfunction "KL_2") (pintype "passive"))
    )
    (net (code "62") (name "Net-(SOBE-C)") (class "Default")
      (node (ref "R13") (pin "1") (pinfunction "1_1") (pintype "passive"))
      (node (ref "SOBE") (pin "K") (pinfunction "C_K") (pintype "passive"))
    )
    (net (code "63") (name "Net-(T1-B)") (class "Default")
      (node (ref "R1") (pin "1") (pinfunction "1_1") (pintype "passive"))
      (node (ref "T1") (pin "1") (pinfunction "B_1") (pintype "passive"))
    )
    (net (code "64") (name "Net-(TRAFO_CANA-KL)") (class "Default")
      (node (ref "F1_CANCELAS") (pin "1") (pinfunction "1_1") (pintype "passive"))
      (node (ref "TRAFO_CAN") (pin "1") (pinfunction "KL_1") (pintype "passive"))
    )
    (net (code "65") (name "Net-(TRAFO_CANB-KL)") (class "Default")
      (node (ref "D15") (pin "A") (pinfunction "A_A") (pintype "passive"))
      (node (ref "D6") (pin "C") (pinfunction "C_C") (pintype "passive"))
      (node (ref "TRAFO_CAN") (pin "2") (pinfunction "KL_2") (pintype "passive"))
    )
    (net (code "66") (name "Net-(VREG1-IN)") (class "Default")
      (node (ref "C8") (pin "+") (pinfunction "+_+") (pintype "passive"))
      (node (ref "D11") (pin "C") (pinfunction "C_C") (pintype "passive"))
      (node (ref "D12") (pin "C") (pinfunction "C_C") (pintype "passive"))
      (node (ref "VREG1") (pin "1") (pinfunction "IN_1") (pintype "power_in"))
    )
    (net (code "67") (name "OPT_AUDIO_FALA") (class "Default")
      (node (ref "COM1") (pin "16") (pinfunction "16_16") (pintype "passive"))
      (node (ref "ULN1") (pin "1") (pinfunction "1_1") (pintype "bidirectional"))
    )
    (net (code "68") (name "OPT_AUDIO_LIGA") (class "Default")
      (node (ref "COM1") (pin "14") (pinfunction "14_14") (pintype "passive"))
      (node (ref "R50") (pin "2") (pinfunction "2_2") (pintype "passive"))
    )
    (net (code "69") (name "OPT_DESCE") (class "Default")
      (node (ref "COM1") (pin "10") (pinfunction "10_10") (pintype "passive"))
      (node (ref "ULN1") (pin "3") (pinfunction "3_3") (pintype "bidirectional"))
    )
    (net (code "70") (name "OPT_FREIO") (class "Default")
      (node (ref "COM1") (pin "8") (pinfunction "8_8") (pintype "passive"))
      (node (ref "ULN1") (pin "4") (pinfunction "4_4") (pintype "bidirectional"))
    )
    (net (code "71") (name "OPT_LIGA") (class "Default")
      (node (ref "COM1") (pin "6") (pinfunction "6_6") (pintype "passive"))
      (node (ref "ULN1") (pin "5") (pinfunction "5_5") (pintype "bidirectional"))
    )
    (net (code "72") (name "OPT_SOBE") (class "Default")
      (node (ref "COM1") (pin "12") (pinfunction "12_12") (pintype "passive"))
      (node (ref "ULN1") (pin "2") (pinfunction "2_2") (pintype "bidirectional"))
    )
    (net (code "73") (name "PANTOGRAFICA") (class "Default")
      (node (ref "PORTA_CABINE") (pin "11") (pinfunction "O_11") (pintype "passive"))
      (node (ref "R23") (pin "2") (pinfunction "2_2") (pintype "passive"))
    )
    (net (code "74") (name "PORTA_CABINE") (class "Default")
      (node (ref "PORTA") (pin "1") (pinfunction "KL_1") (pintype "passive"))
      (node (ref "R12") (pin "2") (pinfunction "2_2") (pintype "passive"))
      (node (ref "ULN1") (pin "8") (pinfunction "8_8") (pintype "bidirectional"))
    )
    (net (code "75") (name "RELE_FALAR") (class "Default")
      (node (ref "RELE_IN_AUDIO") (pin "1") (pinfunction "+_1") (pintype "passive"))
      (node (ref "ULN1") (pin "18") (pinfunction "18_18") (pintype "bidirectional"))
    )
    (net (code "76") (name "RL_INF") (class "Default")
      (node (ref "RL_FIM_INFERIOR") (pin "16") (pinfunction "-_16") (pintype "passive"))
      (node (ref "ULN1") (pin "12") (pinfunction "12_12") (pintype "bidirectional"))
    )
    (net (code "77") (name "RL_PT_CABINE") (class "Default")
      (node (ref "PORTA_CABINE") (pin "16") (pinfunction "-_16") (pintype "passive"))
      (node (ref "ULN1") (pin "11") (pinfunction "11_11") (pintype "bidirectional"))
    )
    (net (code "78") (name "RL_SUP") (class "Default")
      (node (ref "RL_FIM_SUPERIOR") (pin "16") (pinfunction "-_16") (pintype "passive"))
      (node (ref "ULN1") (pin "13") (pinfunction "13_13") (pintype "bidirectional"))
    )
    (net (code "79") (name "RS485-A") (class "Default")
      (node (ref "COM1") (pin "17") (pinfunction "17_17") (pintype "passive"))
      (node (ref "U$1") (pin "2") (pinfunction "2_2") (pintype "bidirectional"))
      (node (ref "X1") (pin "2") (pinfunction "KL_2") (pintype "passive"))
    )
    (net (code "80") (name "RS485-B") (class "Default")
      (node (ref "COM1") (pin "19") (pinfunction "19_19") (pintype "passive"))
      (node (ref "U$1") (pin "1") (pinfunction "1_1") (pintype "bidirectional"))
      (node (ref "X1") (pin "1") (pinfunction "KL_1") (pintype "passive"))
    )
    (net (code "81") (name "SAIDA-AUDIO") (class "Default")
      (node (ref "C1") (pin "-") (pinfunction "-_-") (pintype "passive"))
      (node (ref "RELE_IN_AUDIO") (pin "6") (pinfunction "O_6") (pintype "passive"))
      (node (ref "RELE_IN_AUDIO") (pin "9") (pinfunction "S_9") (pintype "passive"))
    )
    (net (code "82") (name "SENSOR1") (class "Default")
      (node (ref "R9") (pin "2") (pinfunction "2_2") (pintype "passive"))
      (node (ref "S2") (pin "1") (pinfunction "KL_1") (pintype "passive"))
    )
    (net (code "83") (name "SENSOR2") (class "Default")
      (node (ref "R24") (pin "2") (pinfunction "2_2") (pintype "passive"))
      (node (ref "S3") (pin "1") (pinfunction "KL_1") (pintype "passive"))
    )
    (net (code "84") (name "SENSOR3") (class "Default")
      (node (ref "R25") (pin "2") (pinfunction "2_2") (pintype "passive"))
      (node (ref "S4") (pin "1") (pinfunction "KL_1") (pintype "passive"))
    )
    (net (code "85") (name "SUP") (class "Default")
      (node (ref "R10") (pin "2") (pinfunction "2_2") (pintype "passive"))
      (node (ref "U$1") (pin "3") (pinfunction "3_3") (pintype "bidirectional"))
      (node (ref "ULN1") (pin "6") (pinfunction "6_6") (pintype "bidirectional"))
      (node (ref "X1") (pin "3") (pinfunction "KL_3") (pintype "passive"))
    )
    (net (code "86") (name "unconnected-(CTT-FREIO-PadO)") (class "Default")
      (node (ref "CTT-FREIO") (pin "O") (pinfunction "O_O") (pintype "passive"))
    )
    (net (code "87") (name "unconnected-(CTT-LIGA-PadO)") (class "Default")
      (node (ref "CTT-LIGA") (pin "O") (pinfunction "O_O") (pintype "passive"))
    )
    (net (code "88") (name "unconnected-(PORTA_CABINEB-S-Pad8)") (class "Default")
      (node (ref "PORTA_CABINE") (pin "8") (pinfunction "S_8") (pintype "passive"))
    )
    (net (code "89") (name "unconnected-(PORTA_CABINEC-S-Pad9)") (class "Default")
      (node (ref "PORTA_CABINE") (pin "9") (pinfunction "S_9") (pintype "passive"))
    )
    (net (code "90") (name "unconnected-(RL_FIM_INFERIORB-S-Pad8)") (class "Default")
      (node (ref "RL_FIM_INFERIOR") (pin "8") (pinfunction "S_8") (pintype "passive"))
    )
    (net (code "91") (name "unconnected-(RL_FIM_INFERIORC-S-Pad9)") (class "Default")
      (node (ref "RL_FIM_INFERIOR") (pin "9") (pinfunction "S_9") (pintype "passive"))
    )
    (net (code "92") (name "unconnected-(RL_FIM_SUPERIORB-S-Pad8)") (class "Default")
      (node (ref "RL_FIM_SUPERIOR") (pin "8") (pinfunction "S_8") (pintype "passive"))
    )
    (net (code "93") (name "unconnected-(RL_FIM_SUPERIORC-S-Pad9)") (class "Default")
      (node (ref "RL_FIM_SUPERIOR") (pin "9") (pinfunction "S_9") (pintype "passive"))
    )
  )
)
